# Transformer_FrontEnd_1.net
KiCad netlist of a schematic drawn in Altium Designer
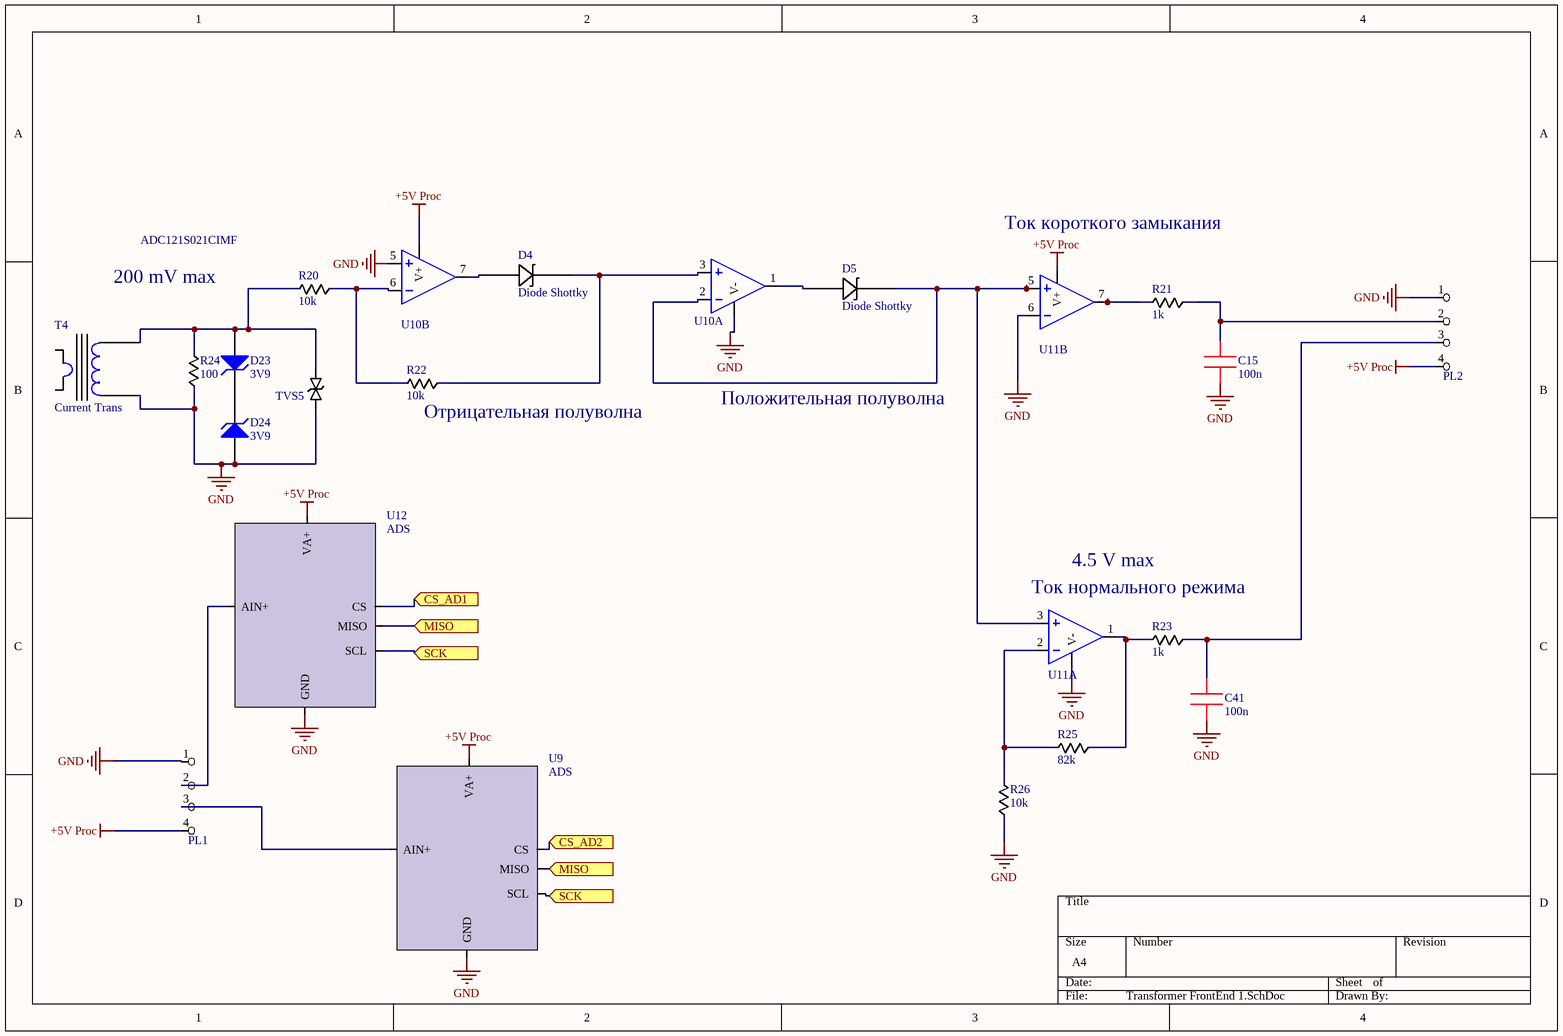
[diagram p0: Transformer FrontEnd 1.SchDoc]

(export (version "E")
  (design (tool "Eeschema 10.0.6"))
  (components
    (comp (ref "C15")
      (value "100n")
      (footprint "0603")
      (description "CC0603KRX7R9BB104")
      (libsource (lib "kontr") (part "0603 CAP"))
    )
    (comp (ref "C41")
      (value "100n")
      (footprint "0603")
      (description "CC0603KRX7R9BB104")
      (libsource (lib "kontr") (part "0603 CAP"))
    )
    (comp (ref "D4")
      (value "Diode Shottky")
      (footprint "SOD523")
      (description "RB751S40T1G")
      (libsource (lib "kontr") (part "Diode Shottky"))
    )
    (comp (ref "D5")
      (value "Diode Shottky")
      (footprint "SOD523")
      (description "RB751S40T1G")
      (libsource (lib "kontr") (part "Diode Shottky"))
    )
    (comp (ref "D23")
      (value "3V9")
      (footprint "PcbLib1:SOD80C")
      (description "BZV55-C3V9,115")
      (libsource (lib "Miscellaneous Devices") (part "D Zener"))
    )
    (comp (ref "D24")
      (value "3V9")
      (footprint "PcbLib1:SOD80C")
      (description "BZV55-C3V9,115")
      (libsource (lib "Miscellaneous Devices") (part "D Zener"))
    )
    (comp (ref "PL1")
      (value "plug")
      (footprint "PLS 4")
      (description "PLS-4R (DS1022-1x4R)")
      (libsource (lib "kontr") (part "PLS-4R"))
    )
    (comp (ref "PL2")
      (value "plug")
      (footprint "PLS 4")
      (description "PLS-4R (DS1022-1x4R)")
      (libsource (lib "kontr") (part "PLS-4R"))
    )
    (comp (ref "R20")
      (value "10k")
      (footprint "0603")
      (description "RT0603FRE0710KL")
      (libsource (lib "kontr") (part "0603 RES"))
    )
    (comp (ref "R21")
      (value "1k")
      (footprint "0603")
      (description "RC0603FR-071KL")
      (libsource (lib "kontr") (part "0603 RES"))
    )
    (comp (ref "R22")
      (value "10k")
      (footprint "0603")
      (description "RT0603FRE0710KL")
      (libsource (lib "kontr") (part "0603 RES"))
    )
    (comp (ref "R23")
      (value "1k")
      (footprint "0603")
      (description "RC0603FR-071KL")
      (libsource (lib "kontr") (part "0603 RES"))
    )
    (comp (ref "R24")
      (value "100")
      (footprint "1206")
      (description "RT1206BRD07100RL")
      (libsource (lib "kontr") (part "SMD Resistor"))
    )
    (comp (ref "R25")
      (value "82k")
      (footprint "0603")
      (description "ERJ3EKF8202V")
      (libsource (lib "kontr") (part "0603 RES"))
    )
    (comp (ref "R26")
      (value "10k")
      (footprint "0603")
      (description "RT0603FRE0710KL")
      (libsource (lib "kontr") (part "0603 RES"))
    )
    (comp (ref "T4")
      (value "Current Trans")
      (footprint "Talema")
      (description "AC-1005")
      (libsource (lib "kontr") (part "Current Trans"))
    )
    (comp (ref "TVS5")
      (value "SMAJ5.0CA")
      (footprint "DO-214AC")
      (libsource (lib "kontr") (part "SMAJ5.0CA"))
    )
    (comp (ref "U9")
      (value "ADS")
      (footprint "SOT23 - 6")
      (description "ADC121S021CIMF")
      (libsource (lib "kontr") (part "ADS"))
    )
    (comp (ref "U10")
      (value "OPAMP 2Ch")
      (footprint "SOIC 8")
      (description "TS272IDT")
      (libsource (lib "kontr") (part "OPAMP 2Ch"))
    )
    (comp (ref "U11")
      (value "OPAMP 2Ch")
      (footprint "SOIC 8")
      (description "TS272IDT")
      (libsource (lib "kontr") (part "OPAMP 2Ch"))
    )
    (comp (ref "U12")
      (value "ADS")
      (footprint "SOT23 - 6")
      (description "ADC121S021CIMF")
      (libsource (lib "kontr") (part "ADS"))
    )
  )
  (nets
    (net (code "1") (name "+5V Proc") (class "Default")
      (node (ref "PL1") (pin "4") (pinfunction "2_4") (pintype "passive"))
      (node (ref "PL2") (pin "4") (pinfunction "2_4") (pintype "passive"))
      (node (ref "U10") (pin "8") (pinfunction "V+_8") (pintype "passive"))
      (node (ref "U11") (pin "8") (pinfunction "V+_8") (pintype "passive"))
      (node (ref "U12") (pin "1") (pinfunction "VA+_1") (pintype "passive"))
      (node (ref "U9") (pin "1") (pinfunction "VA+_1") (pintype "passive"))
    )
    (net (code "2") (name "/CS_AD1") (class "Default")
      (node (ref "U12") (pin "6") (pinfunction "CS_6") (pintype "passive"))
    )
    (net (code "3") (name "/CS_AD2") (class "Default")
      (node (ref "U9") (pin "6") (pinfunction "CS_6") (pintype "passive"))
    )
    (net (code "4") (name "/MISO") (class "Default")
      (node (ref "U12") (pin "5") (pinfunction "MISO_5") (pintype "passive"))
      (node (ref "U9") (pin "5") (pinfunction "MISO_5") (pintype "passive"))
    )
    (net (code "5") (name "/SCK") (class "Default")
      (node (ref "U12") (pin "4") (pinfunction "SCL_4") (pintype "passive"))
      (node (ref "U9") (pin "4") (pinfunction "SCL_4") (pintype "passive"))
    )
    (net (code "6") (name "GND") (class "Default")
      (node (ref "C15") (pin "1") (pinfunction "1_1") (pintype "passive"))
      (node (ref "C41") (pin "1") (pinfunction "1_1") (pintype "passive"))
      (node (ref "D24") (pin "1") (pinfunction "A_1") (pintype "passive"))
      (node (ref "PL1") (pin "1") (pinfunction "1_1") (pintype "passive"))
      (node (ref "PL2") (pin "1") (pinfunction "1_1") (pintype "passive"))
      (node (ref "R24") (pin "1") (pintype "passive"))
      (node (ref "R26") (pin "1") (pintype "passive"))
      (node (ref "T4") (pin "2") (pinfunction "2_2") (pintype "passive"))
      (node (ref "TVS5") (pin "1") (pinfunction "1_1") (pintype "passive"))
      (node (ref "U10") (pin "4") (pinfunction "V-_4") (pintype "passive"))
      (node (ref "U10") (pin "5") (pinfunction "+IN_5") (pintype "passive"))
      (node (ref "U11") (pin "4") (pinfunction "V-_4") (pintype "passive"))
      (node (ref "U11") (pin "6") (pinfunction "-IN_6") (pintype "passive"))
      (node (ref "U12") (pin "2") (pinfunction "GND_2") (pintype "passive"))
      (node (ref "U9") (pin "2") (pinfunction "GND_2") (pintype "passive"))
    )
    (net (code "7") (name "Net-(C15-Pad2)") (class "Default")
      (node (ref "C15") (pin "2") (pinfunction "2_2") (pintype "passive"))
      (node (ref "PL2") (pin "2") (pinfunction "2_2") (pintype "passive"))
      (node (ref "R21") (pin "1") (pintype "passive"))
    )
    (net (code "8") (name "Net-(C41-Pad2)") (class "Default")
      (node (ref "C41") (pin "2") (pinfunction "2_2") (pintype "passive"))
      (node (ref "PL2") (pin "3") (pinfunction "1_3") (pintype "passive"))
      (node (ref "R23") (pin "1") (pintype "passive"))
    )
    (net (code "9") (name "Net-(D23-A)") (class "Default")
      (node (ref "D23") (pin "1") (pinfunction "A_1") (pintype "passive"))
      (node (ref "R20") (pin "2") (pintype "passive"))
      (node (ref "R24") (pin "2") (pintype "passive"))
      (node (ref "T4") (pin "1") (pinfunction "1_1") (pintype "passive"))
      (node (ref "TVS5") (pin "2") (pinfunction "2_2") (pintype "passive"))
    )
    (net (code "10") (name "Net-(D23-K)") (class "Default")
      (node (ref "D23") (pin "2") (pinfunction "K_2") (pintype "passive"))
      (node (ref "D24") (pin "2") (pinfunction "K_2") (pintype "passive"))
    )
    (net (code "11") (name "Net-(U9-AIN+)") (class "Default")
      (node (ref "PL1") (pin "3") (pinfunction "1_3") (pintype "passive"))
      (node (ref "U9") (pin "3") (pinfunction "AIN+_3") (pintype "passive"))
    )
    (net (code "12") (name "Net-(U10A-+IN)") (class "Default")
      (node (ref "D4") (pin "2") (pinfunction "2_2") (pintype "passive"))
      (node (ref "R22") (pin "1") (pintype "passive"))
      (node (ref "U10") (pin "3") (pinfunction "+IN_3") (pintype "passive"))
    )
    (net (code "13") (name "Net-(U10A--IN)") (class "Default")
      (node (ref "D5") (pin "2") (pinfunction "2_2") (pintype "passive"))
      (node (ref "U10") (pin "2") (pinfunction "-IN_2") (pintype "passive"))
      (node (ref "U11") (pin "3") (pinfunction "+IN_3") (pintype "passive"))
      (node (ref "U11") (pin "5") (pinfunction "+IN_5") (pintype "passive"))
    )
    (net (code "14") (name "Net-(U10A-OUT)") (class "Default")
      (node (ref "D5") (pin "1") (pinfunction "1_1") (pintype "passive"))
      (node (ref "U10") (pin "1") (pinfunction "OUT_1") (pintype "passive"))
    )
    (net (code "15") (name "Net-(U10B--IN)") (class "Default")
      (node (ref "R20") (pin "1") (pintype "passive"))
      (node (ref "R22") (pin "2") (pintype "passive"))
      (node (ref "U10") (pin "6") (pinfunction "-IN_6") (pintype "passive"))
    )
    (net (code "16") (name "Net-(U10B-OUT)") (class "Default")
      (node (ref "D4") (pin "1") (pinfunction "1_1") (pintype "passive"))
      (node (ref "U10") (pin "7") (pinfunction "OUT_7") (pintype "passive"))
    )
    (net (code "17") (name "Net-(U11A--IN)") (class "Default")
      (node (ref "R25") (pin "2") (pintype "passive"))
      (node (ref "R26") (pin "2") (pintype "passive"))
      (node (ref "U11") (pin "2") (pinfunction "-IN_2") (pintype "passive"))
    )
    (net (code "18") (name "Net-(U11A-OUT)") (class "Default")
      (node (ref "R23") (pin "2") (pintype "passive"))
      (node (ref "R25") (pin "1") (pintype "passive"))
      (node (ref "U11") (pin "1") (pinfunction "OUT_1") (pintype "passive"))
    )
    (net (code "19") (name "Net-(U11B-OUT)") (class "Default")
      (node (ref "R21") (pin "2") (pintype "passive"))
      (node (ref "U11") (pin "7") (pinfunction "OUT_7") (pintype "passive"))
    )
    (net (code "20") (name "Net-(U12-AIN+)") (class "Default")
      (node (ref "PL1") (pin "2") (pinfunction "2_2") (pintype "passive"))
      (node (ref "U12") (pin "3") (pinfunction "AIN+_3") (pintype "passive"))
    )
  )
)
